# ver060_Power.net
KiCad netlist of a schematic drawn in Altium Designer
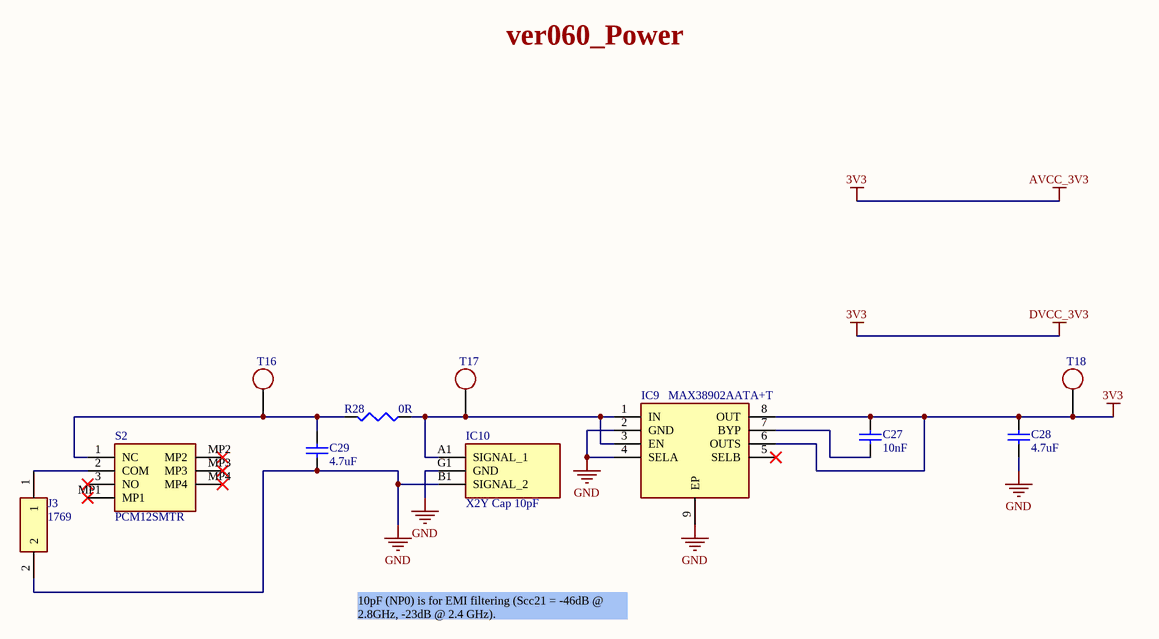
[diagram p0: ver060_Power.SchDoc]

(export (version "E")
  (design (tool "Eeschema 10.0.6"))
  (components
    (comp (ref "C27")
      (value "10nF")
      (footprint "1608[0603]")
      (description "Capacitor (Semiconductor SIM Model)")
      (fields (field (name "Comment") "Cap Semi") (field (name "PUBLISHER") "Altium Limited"))
      (libsource (lib "Miscellaneous Devices") (part "Cap Semi"))
    )
    (comp (ref "C28")
      (value "4.7uF")
      (footprint "1608[0603]")
      (description "Capacitor (Semiconductor SIM Model)")
      (fields (field (name "Comment") "Cap Semi") (field (name "PUBLISHER") "Altium Limited"))
      (libsource (lib "Miscellaneous Devices") (part "Cap Semi"))
    )
    (comp (ref "C29")
      (value "4.7uF")
      (footprint "1608[0603]")
      (description "Capacitor (Semiconductor SIM Model)")
      (fields (field (name "Comment") "Cap Semi") (field (name "PUBLISHER") "Altium Limited"))
      (libsource (lib "Miscellaneous Devices") (part "Cap Semi"))
    )
    (comp (ref "IC9")
      (value "MAX38902AATA+T")
      (footprint "nanowire:SON50P200X200X80-9N-D")
      (description "Integrated Circuit")
      (fields (field (name "MOUSER PART NUMBER") "700-MAX38902AATA+T"))
      (libsource (lib "*") (part "MAX38902AATA+T"))
    )
    (comp (ref "IC10")
      (value "X2Y Cap 10pF")
      (footprint "nanowire:500X14W102MV4T")
      (description "Integrated Circuit")
      (fields
        (field (name "MANUFACTURER_PART_NUMBER") "500X14W102MV4T")
        (field (name "MOUSER PART NUMBER") "605-500X14W102MV4T")
      )
      (libsource (lib "nanowire") (part "500X14W102MV4T"))
    )
    (comp (ref "J3")
      (value "1769")
      (footprint "nanowire:1769")
      (description "Connector")
      (fields (field (name "MOUSER PART NUMBER") "485-1769"))
      (libsource (lib "*") (part "1769"))
    )
    (comp (ref "R28")
      (value "0R")
      (footprint "J1-0603")
      (description "Resistor")
      (fields (field (name "Comment") "Res3") (field (name "PUBLISHER") "Altium Limited"))
      (libsource (lib "Miscellaneous Devices") (part "Res3"))
    )
    (comp (ref "S2")
      (value "PCM12SMTR")
      (footprint "nanowire:PCM12SMTR")
      (description "Switch")
      (fields (field (name "MOUSER PART NUMBER") "611-PCM12SMTR"))
      (libsource (lib "*") (part "PCM12SMTR"))
    )
    (comp (ref "T16")
      (value "TP_SMT")
      (footprint "TP_SMT_Round_0.6x0.6")
      (libsource (lib "nanowire") (part "TP_SMT"))
    )
    (comp (ref "T17")
      (value "TP_SMT")
      (footprint "TP_SMT_Round_0.6x0.6")
      (libsource (lib "nanowire") (part "TP_SMT"))
    )
    (comp (ref "T18")
      (value "TP_SMT")
      (footprint "TP_SMT_Round_0.6x0.6")
      (libsource (lib "nanowire") (part "TP_SMT"))
    )
  )
  (nets
    (net (code "1") (name "3V3") (class "Default")
      (node (ref "C27") (pin "1") (pinfunction "1_1") (pintype "passive"))
      (node (ref "C28") (pin "1") (pinfunction "1_1") (pintype "passive"))
      (node (ref "IC9") (pin "6") (pinfunction "OUTS_6") (pintype "passive"))
      (node (ref "IC9") (pin "8") (pinfunction "OUT_8") (pintype "passive"))
      (node (ref "T18") (pin "1") (pinfunction "1_1") (pintype "passive"))
    )
    (net (code "2") (name "GND") (class "Default")
      (node (ref "C28") (pin "2") (pinfunction "2_2") (pintype "passive"))
      (node (ref "C29") (pin "2") (pinfunction "2_2") (pintype "passive"))
      (node (ref "IC10") (pin "B1") (pinfunction "SIGNAL_2_B1") (pintype "passive"))
      (node (ref "IC10") (pin "G1") (pinfunction "GND_G1") (pintype "passive"))
      (node (ref "IC9") (pin "2") (pinfunction "GND_2") (pintype "passive"))
      (node (ref "IC9") (pin "4") (pinfunction "SELA_4") (pintype "passive"))
      (node (ref "IC9") (pin "9") (pinfunction "EP_9") (pintype "passive"))
      (node (ref "J3") (pin "2") (pinfunction "2_2") (pintype "passive"))
    )
    (net (code "3") (name "Net-(IC9-BYP)") (class "Default")
      (node (ref "C27") (pin "2") (pinfunction "2_2") (pintype "passive"))
      (node (ref "IC9") (pin "7") (pinfunction "BYP_7") (pintype "passive"))
    )
    (net (code "4") (name "Net-(IC10-SIGNAL_1)") (class "Default")
      (node (ref "IC10") (pin "A1") (pinfunction "SIGNAL_1_A1") (pintype "passive"))
      (node (ref "IC9") (pin "1") (pinfunction "IN_1") (pintype "passive"))
      (node (ref "IC9") (pin "3") (pinfunction "EN_3") (pintype "passive"))
      (node (ref "R28") (pin "1") (pinfunction "1_1") (pintype "passive"))
      (node (ref "T17") (pin "1") (pinfunction "1_1") (pintype "passive"))
    )
    (net (code "5") (name "Net-(S2-COM)") (class "Default")
      (node (ref "J3") (pin "1") (pinfunction "1_1") (pintype "passive"))
      (node (ref "S2") (pin "2") (pinfunction "COM_2") (pintype "passive"))
    )
    (net (code "6") (name "Net-(S2-NC)") (class "Default")
      (node (ref "C29") (pin "1") (pinfunction "1_1") (pintype "passive"))
      (node (ref "R28") (pin "2") (pinfunction "2_2") (pintype "passive"))
      (node (ref "S2") (pin "1") (pinfunction "NC_1") (pintype "passive"))
      (node (ref "T16") (pin "1") (pinfunction "1_1") (pintype "passive"))
    )
    (net (code "7") (name "unconnected-(IC9-SELB-Pad5)") (class "Default")
      (node (ref "IC9") (pin "5") (pinfunction "SELB_5") (pintype "passive+no_connect"))
    )
    (net (code "8") (name "unconnected-(S2-NO-Pad3)") (class "Default")
      (node (ref "S2") (pin "3") (pinfunction "NO_3") (pintype "passive+no_connect"))
    )
    (net (code "9") (name "unconnected-(S2-PadMP1)") (class "Default")
      (node (ref "S2") (pin "MP1") (pinfunction "MP1_MP1") (pintype "passive+no_connect"))
    )
    (net (code "10") (name "unconnected-(S2-PadMP2)") (class "Default")
      (node (ref "S2") (pin "MP2") (pinfunction "MP2_MP2") (pintype "passive+no_connect"))
    )
    (net (code "11") (name "unconnected-(S2-PadMP3)") (class "Default")
      (node (ref "S2") (pin "MP3") (pinfunction "MP3_MP3") (pintype "passive+no_connect"))
    )
    (net (code "12") (name "unconnected-(S2-PadMP4)") (class "Default")
      (node (ref "S2") (pin "MP4") (pinfunction "MP4_MP4") (pintype "passive+no_connect"))
    )
  )
)
